# buck_boost.net
KiCad netlist of a schematic drawn in Altium Designer
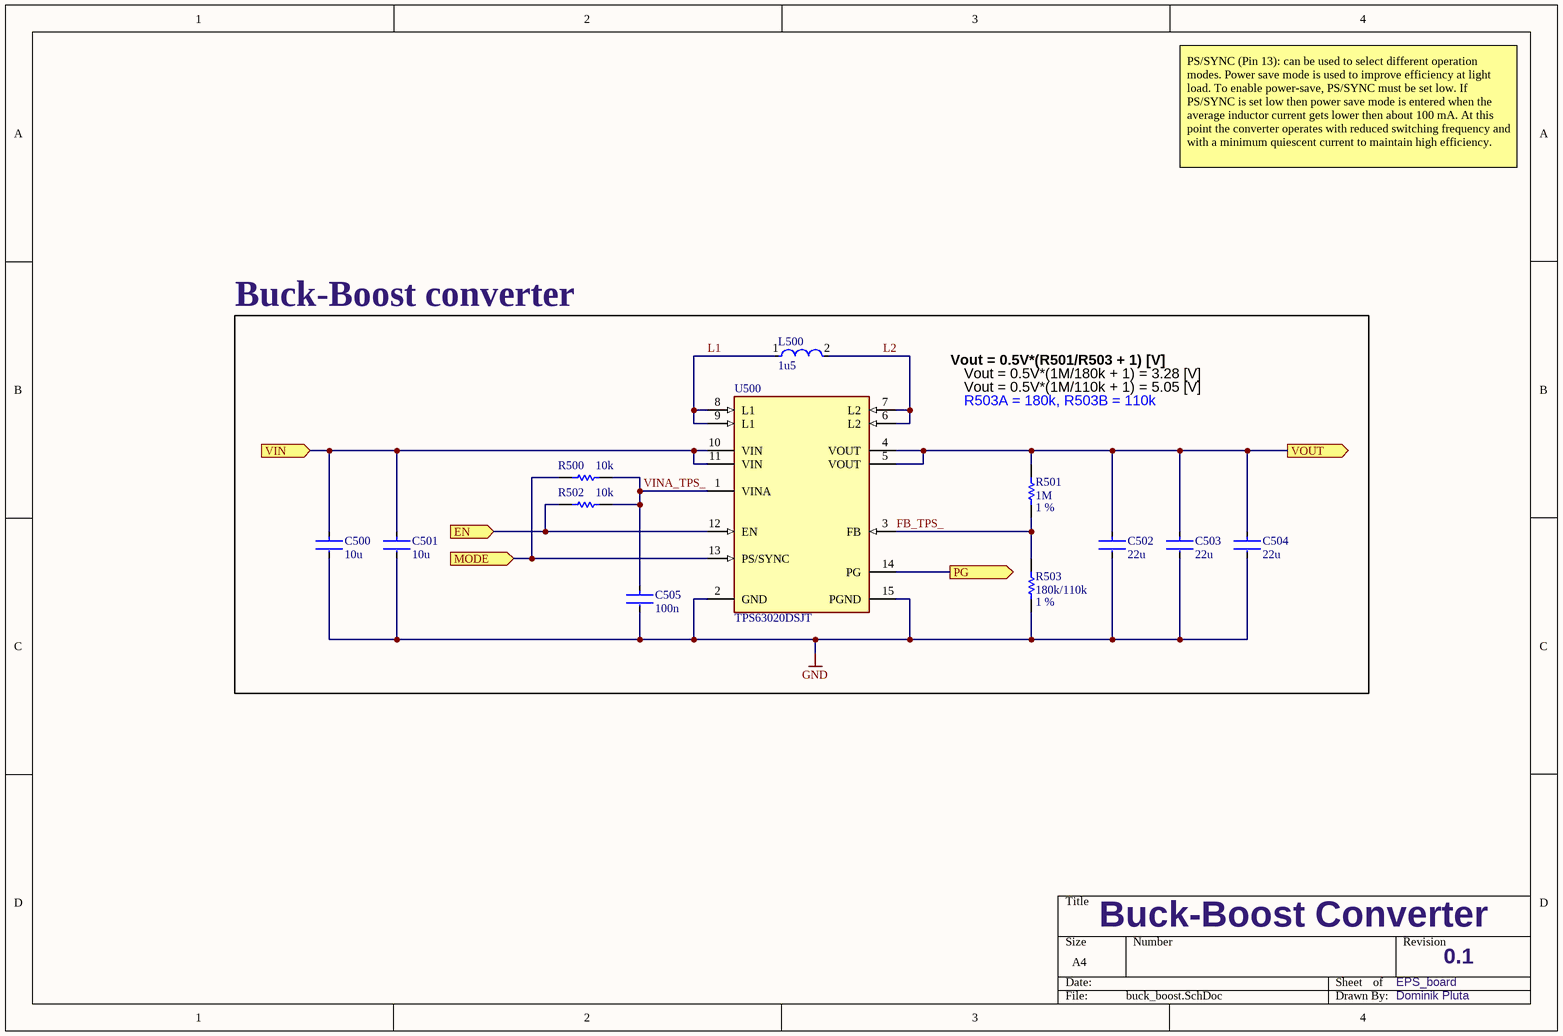
[diagram p0: buck_boost.SchDoc]

(export (version "E")
  (design (tool "Eeschema 10.0.6"))
  (components
    (comp (ref "C500")
      (value "10u")
      (footprint "FP-C0603C-CF-MFG")
      (description "CAP 10 μF 20% 6.3V, 0603, X5R ceramic, eg: GRM188R60J106ME84D")
      (fields (field (name "TOLERANCE") "20%") (field (name "MANUFACTURER") "MURATA"))
      (libsource (lib "Altium Content Vault") (part "b4654b650e69147ec39a6b967a45e02"))
    )
    (comp (ref "C501")
      (value "10u")
      (footprint "FP-C0603C-CF-MFG")
      (description "CAP 10 μF 20% 6.3V, 0603, X5R ceramic, eg: GRM188R60J106ME84D")
      (fields (field (name "TOLERANCE") "20%") (field (name "MANUFACTURER") "MURATA"))
      (libsource (lib "Altium Content Vault") (part "b4654b650e69147ec39a6b967a45e02"))
    )
    (comp (ref "C502")
      (value "22u")
      (footprint "FP-C0603C-CF-MFG")
      (description "CAP 22 μF 20% 6.3V, 0603, X5R ceramic, eg: GRM188R60J226MEAOL")
      (fields (field (name "TOLERANCE") "20%") (field (name "MANUFACTURER") "MURATA"))
      (libsource (lib "Altium Content Vault") (part "b4654b650e69147ec39a6b967a45e02"))
    )
    (comp (ref "C503")
      (value "22u")
      (footprint "FP-C0603C-CF-MFG")
      (description "CAP 22 μF 20% 6.3V, 0603, X5R ceramic, eg: GRM188R60J226MEAOL")
      (fields (field (name "TOLERANCE") "20%") (field (name "MANUFACTURER") "MURATA"))
      (libsource (lib "Altium Content Vault") (part "b4654b650e69147ec39a6b967a45e02"))
    )
    (comp (ref "C504")
      (value "22u")
      (footprint "FP-C0603C-CF-MFG")
      (description "CAP 22 μF 20% 6.3V, 0603, X5R ceramic, eg: GRM188R60J226MEAOL")
      (fields (field (name "TOLERANCE") "20%") (field (name "MANUFACTURER") "MURATA"))
      (libsource (lib "Altium Content Vault") (part "b4654b650e69147ec39a6b967a45e02"))
    )
    (comp (ref "C505")
      (value "100n")
      (footprint "FP-C0603C-CF-MFG")
      (description "CAP 0.1 μF, X5R or X7R ceramic")
      (fields (field (name "TOLERANCE") "10"))
      (libsource (lib "Altium Content Vault") (part "b4654b650e69147ec39a6b967a45e02"))
    )
    (comp (ref "L500")
      (value "1u5")
      (footprint "FP-IHLP-1616BZ-FP_1_8545x-MFG")
      (description "XFL4020-152ML\r\n1.5uH 4.6A 15.8mΩ 20%")
      (fields (field (name "TOLERANCE") "20%") (field (name "MANUFACTURER PART NUMBER") "XFL4020-152ML"))
      (libsource (lib "Altium Content Vault") (part "725321dda6339637d4d059423bc1c3c"))
    )
    (comp (ref "R500")
      (value "10k")
      (footprint "RESC0603(1608)_N")
      (description "10k 0.1W 5% 0603 SMD")
      (fields (field (name "TOLERANCE") "5 %") (field (name "POWER") "0.1 W"))
      (libsource (lib "Altium Content Vault") (part "RES"))
    )
    (comp (ref "R501")
      (value "1M")
      (footprint "RESC0603(1608)_N")
      (description "1M 0.1W 1% 0603  SMD")
      (fields (field (name "TOLERANCE") "1 %") (field (name "POWER") "0.1 W"))
      (libsource (lib "Altium Content Vault") (part "RES"))
    )
    (comp (ref "R502")
      (value "10k")
      (footprint "RESC0603(1608)_N")
      (description "10k 0.1W 5% 0603 SMD")
      (fields (field (name "TOLERANCE") "5 %") (field (name "POWER") "0.1 W"))
      (libsource (lib "Altium Content Vault") (part "RES"))
    )
    (comp (ref "R503")
      (value "180k/110k")
      (footprint "RESC0603(1608)_N")
      (description "180k/110k 0.1W 1% 0603 (1608 Metric)  SMD")
      (fields (field (name "TOLERANCE") "1 %") (field (name "POWER") "0.1 W"))
      (libsource (lib "Altium Content Vault") (part "RES"))
    )
    (comp (ref "U500")
      (value "TPS63020DSJT")
      (footprint "FP-DSJ0014A-MFG")
      (description "IC REG BCK BST ADJ 3.5A 14VSON")
      (fields
        (field (name "MANUFACTURER") "Texas Instruments")
        (field (name "OCTOPART") "https://octopart.com/tps63020dsjt-texas+instruments-12976119")
      )
      (libsource (lib "TPS63020DSJT") (part "CMP-2000-07282-2"))
    )
  )
  (nets
    (net (code "1") (name "/EN") (class "Default")
      (node (ref "R502") (pin "2") (pinfunction "2_2") (pintype "passive"))
      (node (ref "U500") (pin "12") (pinfunction "EN_12") (pintype "input"))
    )
    (net (code "2") (name "/FB_TPS_") (class "Default")
      (node (ref "R501") (pin "1") (pinfunction "1_1") (pintype "passive"))
      (node (ref "R503") (pin "2") (pinfunction "2_2") (pintype "passive"))
      (node (ref "U500") (pin "3") (pinfunction "FB_3") (pintype "input"))
    )
    (net (code "3") (name "/L1") (class "Default")
      (node (ref "L500") (pin "1") (pinfunction "1_1") (pintype "passive"))
      (node (ref "U500") (pin "8") (pinfunction "L1_8") (pintype "input"))
      (node (ref "U500") (pin "9") (pinfunction "L1_9") (pintype "input"))
    )
    (net (code "4") (name "/L2") (class "Default")
      (node (ref "L500") (pin "2") (pinfunction "2_2") (pintype "passive"))
      (node (ref "U500") (pin "6") (pinfunction "L2_6") (pintype "input"))
      (node (ref "U500") (pin "7") (pinfunction "L2_7") (pintype "input"))
    )
    (net (code "5") (name "/MODE") (class "Default")
      (node (ref "R500") (pin "2") (pinfunction "2_2") (pintype "passive"))
      (node (ref "U500") (pin "13") (pinfunction "PS/SYNC_13") (pintype "input"))
    )
    (net (code "6") (name "/PG") (class "Default")
      (node (ref "U500") (pin "14") (pinfunction "PG_14") (pintype "open_collector"))
    )
    (net (code "7") (name "/VIN") (class "Default")
      (node (ref "C500") (pin "1") (pinfunction "1_1") (pintype "passive"))
      (node (ref "C501") (pin "1") (pinfunction "1_1") (pintype "passive"))
      (node (ref "U500") (pin "10") (pinfunction "VIN_10") (pintype "power_in"))
      (node (ref "U500") (pin "11") (pinfunction "VIN_11") (pintype "power_in"))
    )
    (net (code "8") (name "/VINA_TPS_") (class "Default")
      (node (ref "C505") (pin "1") (pinfunction "1_1") (pintype "passive"))
      (node (ref "R500") (pin "1") (pinfunction "1_1") (pintype "passive"))
      (node (ref "R502") (pin "1") (pinfunction "1_1") (pintype "passive"))
      (node (ref "U500") (pin "1") (pinfunction "VINA_1") (pintype "power_in"))
    )
    (net (code "9") (name "/VOUT") (class "Default")
      (node (ref "C502") (pin "1") (pinfunction "1_1") (pintype "passive"))
      (node (ref "C503") (pin "1") (pinfunction "1_1") (pintype "passive"))
      (node (ref "C504") (pin "1") (pinfunction "1_1") (pintype "passive"))
      (node (ref "R501") (pin "2") (pinfunction "2_2") (pintype "passive"))
      (node (ref "U500") (pin "4") (pinfunction "VOUT_4") (pintype "power_in"))
      (node (ref "U500") (pin "5") (pinfunction "VOUT_5") (pintype "power_in"))
    )
    (net (code "10") (name "GND") (class "Default")
      (node (ref "C500") (pin "2") (pinfunction "2_2") (pintype "passive"))
      (node (ref "C501") (pin "2") (pinfunction "2_2") (pintype "passive"))
      (node (ref "C502") (pin "2") (pinfunction "2_2") (pintype "passive"))
      (node (ref "C503") (pin "2") (pinfunction "2_2") (pintype "passive"))
      (node (ref "C504") (pin "2") (pinfunction "2_2") (pintype "passive"))
      (node (ref "C505") (pin "2") (pinfunction "2_2") (pintype "passive"))
      (node (ref "R503") (pin "1") (pinfunction "1_1") (pintype "passive"))
      (node (ref "U500") (pin "15") (pinfunction "PGND_15") (pintype "power_in"))
      (node (ref "U500") (pin "2") (pinfunction "GND_2") (pintype "power_in"))
    )
  )
)
